# electricals_with_iPod_v2_5.net
KiCad netlist of a schematic drawn in EAGLE
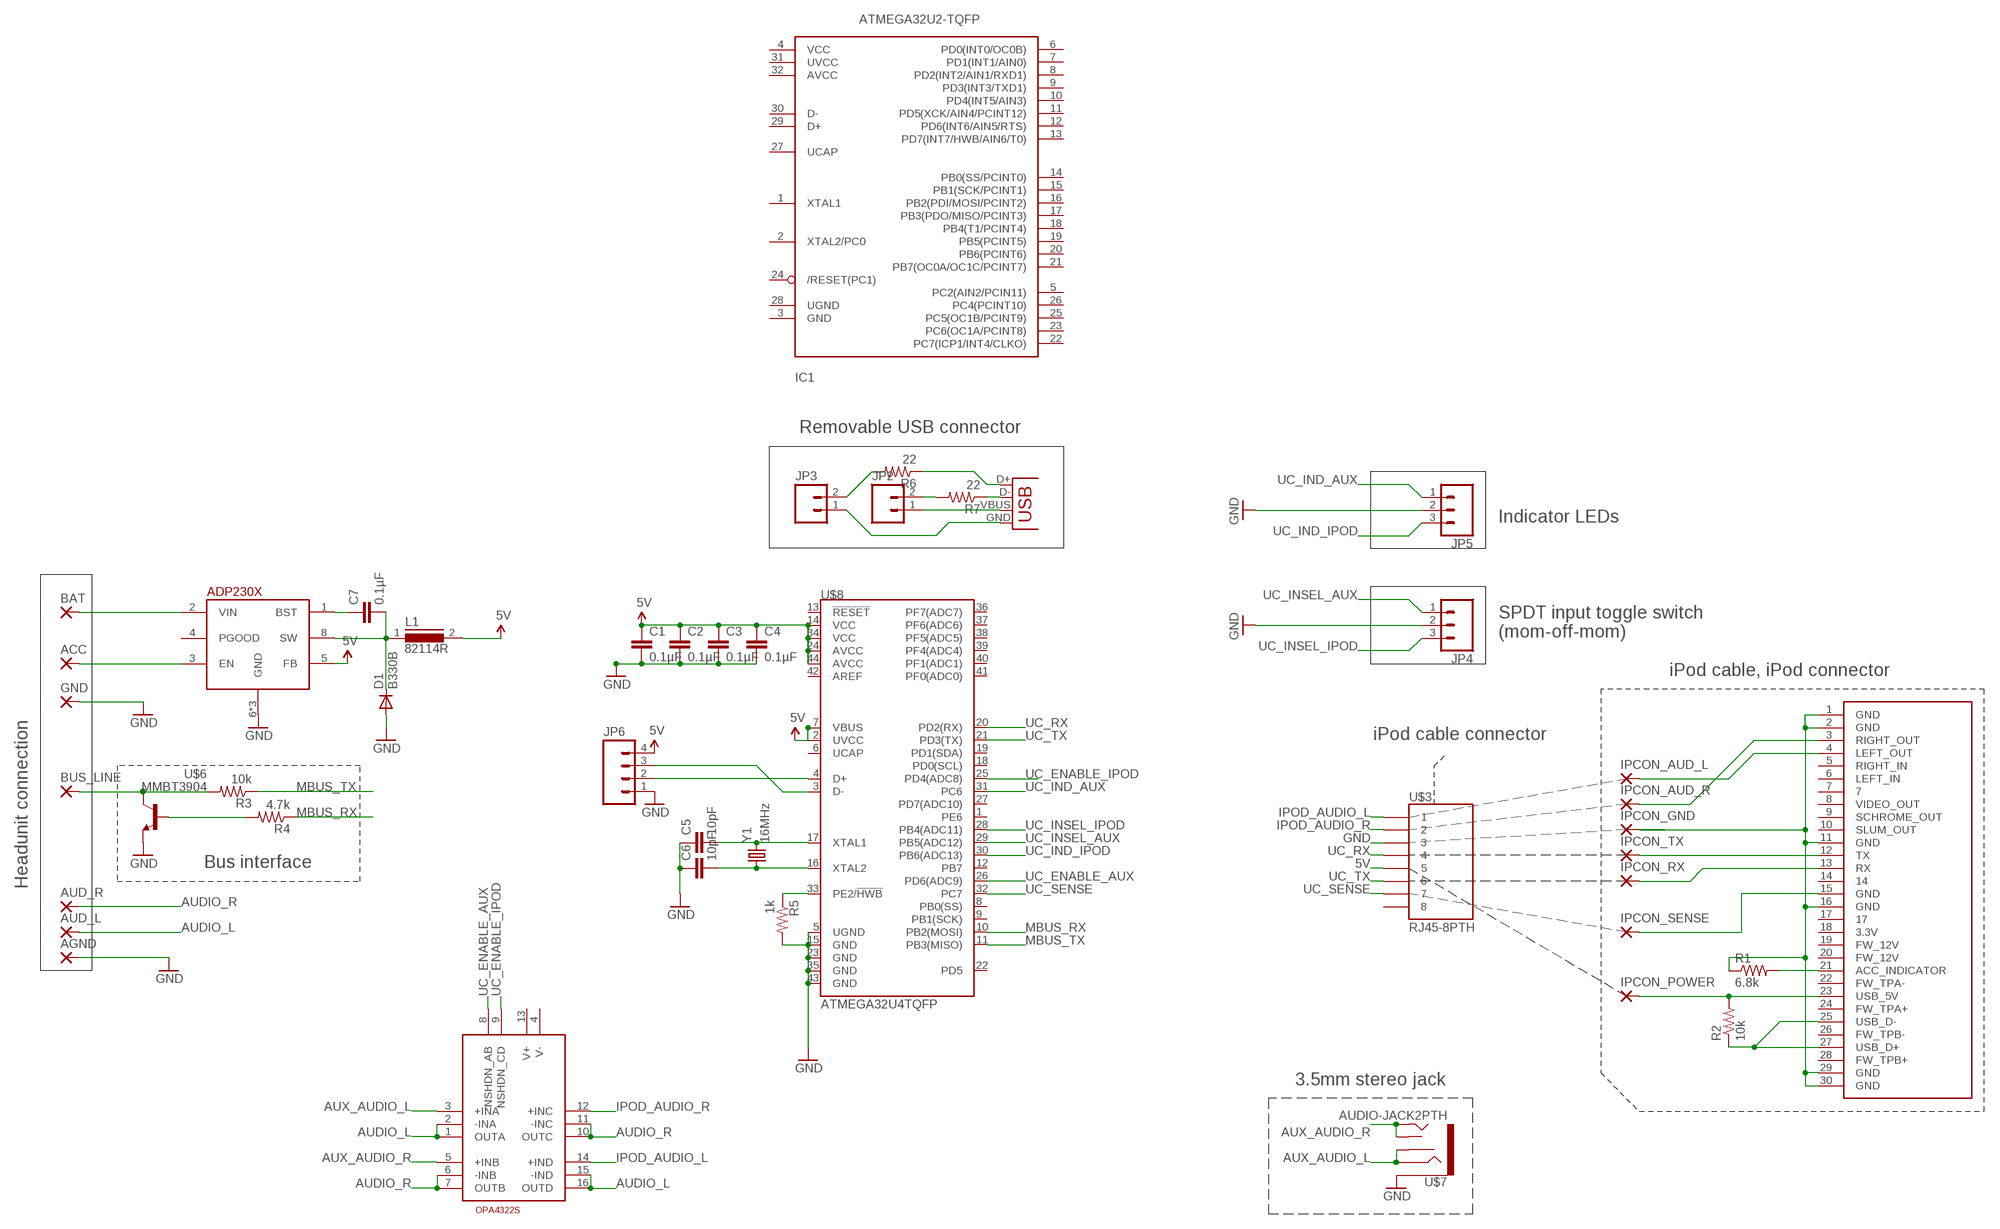
[diagram p0: schematic, sheet 1]

(export (version "E")
  (design (tool "Eeschema 10.0.6"))
  (components
    (comp (ref "ACC")
      (value "1,6/0,9")
      (footprint "eagle-import:1,6_0,9")
      (libsource (lib "eagle-import") (part "1,6/0,9"))
    )
    (comp (ref "AGND")
      (value "1,6/0,9")
      (footprint "eagle-import:1,6_0,9")
      (libsource (lib "eagle-import") (part "1,6/0,9"))
    )
    (comp (ref "AUD_L")
      (value "1,6/0,9")
      (footprint "eagle-import:1,6_0,9")
      (libsource (lib "eagle-import") (part "1,6/0,9"))
    )
    (comp (ref "AUD_R")
      (value "1,6/0,9")
      (footprint "eagle-import:1,6_0,9")
      (libsource (lib "eagle-import") (part "1,6/0,9"))
    )
    (comp (ref "BAT")
      (value "2,54/1,1")
      (footprint "eagle-import:2,54_1,1")
      (libsource (lib "eagle-import") (part "2,54/1,1"))
    )
    (comp (ref "BUS_LINE")
      (value "1,6/0,9")
      (footprint "eagle-import:1,6_0,9")
      (libsource (lib "eagle-import") (part "1,6/0,9"))
    )
    (comp (ref "C1")
      (value "0.1µF")
      (footprint "eagle-import:0805")
      (libsource (lib "eagle-import") (part "CAP0805"))
    )
    (comp (ref "C2")
      (value "0.1µF")
      (footprint "eagle-import:0805")
      (libsource (lib "eagle-import") (part "CAP0805"))
    )
    (comp (ref "C3")
      (value "0.1µF")
      (footprint "eagle-import:0805")
      (libsource (lib "eagle-import") (part "CAP0805"))
    )
    (comp (ref "C4")
      (value "0.1µF")
      (footprint "eagle-import:0805")
      (libsource (lib "eagle-import") (part "CAP0805"))
    )
    (comp (ref "C5")
      (value "10pF")
      (footprint "eagle-import:0805")
      (libsource (lib "eagle-import") (part "CAP0805"))
    )
    (comp (ref "C6")
      (value "10pF")
      (footprint "eagle-import:0805")
      (libsource (lib "eagle-import") (part "CAP0805"))
    )
    (comp (ref "C7")
      (value "0.1µF")
      (footprint "eagle-import:0805")
      (libsource (lib "eagle-import") (part "CAP0805"))
    )
    (comp (ref "D1")
      (value "B330B")
      (footprint "eagle-import:SMA-DIODE_ALT")
      (libsource (lib "eagle-import") (part "DIODESMA-ALT"))
    )
    (comp (ref "GND")
      (value "2,54/1,1")
      (footprint "eagle-import:2,54_1,1")
      (libsource (lib "eagle-import") (part "2,54/1,1"))
    )
    (comp (ref "IC1")
      (value "ATMEGA32U2-TQFP")
      (footprint "eagle-import:TQFP32-08")
      (libsource (lib "eagle-import") (part "ATMEGA32U2-TQFP"))
    )
    (comp (ref "IPCON_AUD_L")
      (value "1,6/0,9")
      (footprint "eagle-import:1,6_0,9")
      (libsource (lib "eagle-import") (part "1,6/0,9"))
    )
    (comp (ref "IPCON_AUD_R")
      (value "1,6/0,9")
      (footprint "eagle-import:1,6_0,9")
      (libsource (lib "eagle-import") (part "1,6/0,9"))
    )
    (comp (ref "IPCON_GND")
      (value "1,6/0,9")
      (footprint "eagle-import:1,6_0,9")
      (libsource (lib "eagle-import") (part "1,6/0,9"))
    )
    (comp (ref "IPCON_POWER")
      (value "1,6/0,9")
      (footprint "eagle-import:1,6_0,9")
      (libsource (lib "eagle-import") (part "1,6/0,9"))
    )
    (comp (ref "IPCON_RX")
      (value "1,6/0,9")
      (footprint "eagle-import:1,6_0,9")
      (libsource (lib "eagle-import") (part "1,6/0,9"))
    )
    (comp (ref "IPCON_SENSE")
      (value "1,6/0,9")
      (footprint "eagle-import:1,6_0,9")
      (libsource (lib "eagle-import") (part "1,6/0,9"))
    )
    (comp (ref "IPCON_TX")
      (value "1,6/0,9")
      (footprint "eagle-import:1,6_0,9")
      (libsource (lib "eagle-import") (part "1,6/0,9"))
    )
    (comp (ref "JP1")
      (value "USBSMD")
      (footprint "eagle-import:USB-MINIB")
      (libsource (lib "eagle-import") (part "USBSMD"))
    )
    (comp (ref "JP2")
      (value "M02POGO_PIN_HOLES_ONLY")
      (footprint "eagle-import:1X02_PP_HOLES_ONLY")
      (libsource (lib "eagle-import") (part "M02POGO_PIN_HOLES_ONLY"))
    )
    (comp (ref "JP3")
      (value "M02POGO_PIN_HOLES_ONLY")
      (footprint "eagle-import:1X02_PP_HOLES_ONLY")
      (libsource (lib "eagle-import") (part "M02POGO_PIN_HOLES_ONLY"))
    )
    (comp (ref "JP4")
      (value "M03LOCK")
      (footprint "eagle-import:1X03_LOCK")
      (libsource (lib "eagle-import") (part "M03LOCK"))
    )
    (comp (ref "JP5")
      (value "M03LOCK")
      (footprint "eagle-import:1X03_LOCK")
      (libsource (lib "eagle-import") (part "M03LOCK"))
    )
    (comp (ref "JP6")
      (value "M04PTH")
      (footprint "eagle-import:1X04")
      (libsource (lib "eagle-import") (part "M04PTH"))
    )
    (comp (ref "L1")
      (value "82114R")
      (footprint "eagle-import:82114R")
      (libsource (lib "eagle-import") (part "82114R"))
    )
    (comp (ref "R1")
      (value "6.8k")
      (footprint "eagle-import:0805")
      (libsource (lib "eagle-import") (part "RESISTOR0805-RES"))
    )
    (comp (ref "R2")
      (value "10k")
      (footprint "eagle-import:0805")
      (libsource (lib "eagle-import") (part "RESISTOR0805-RES"))
    )
    (comp (ref "R3")
      (value "10k")
      (footprint "eagle-import:0805")
      (libsource (lib "eagle-import") (part "RESISTOR0805-RES"))
    )
    (comp (ref "R4")
      (value "4.7k")
      (footprint "eagle-import:0805")
      (libsource (lib "eagle-import") (part "RESISTOR0805-RES"))
    )
    (comp (ref "R5")
      (value "1k")
      (footprint "eagle-import:0805")
      (libsource (lib "eagle-import") (part "RESISTOR0805-RES"))
    )
    (comp (ref "R6")
      (value "22")
      (footprint "eagle-import:0805")
      (libsource (lib "eagle-import") (part "RESISTOR0805-RES"))
    )
    (comp (ref "R7")
      (value "22")
      (footprint "eagle-import:0805")
      (libsource (lib "eagle-import") (part "RESISTOR0805-RES"))
    )
    (comp (ref "U$1")
      (value "IPOD_CONNECTOR_MALE")
      (footprint "eagle-import:IPOD_MALE_CONNECTOR")
      (libsource (lib "eagle-import") (part "IPOD_CONNECTOR_MALE"))
    )
    (comp (ref "U$3")
      (value "RJ45-8PTH")
      (footprint "eagle-import:RJ45-8")
      (libsource (lib "eagle-import") (part "RJ45-8PTH"))
    )
    (comp (ref "U$5")
      (value "ADP230X")
      (footprint "eagle-import:SO8-THERM")
      (libsource (lib "eagle-import") (part "ADP230X"))
    )
    (comp (ref "U$6")
      (value "MMBT3904")
      (footprint "eagle-import:SOT23-3")
      (libsource (lib "eagle-import") (part "MMBT3904"))
    )
    (comp (ref "U$7")
      (value "AUDIO-JACK2PTH")
      (footprint "eagle-import:AUDIO-JACK")
      (libsource (lib "eagle-import") (part "AUDIO-JACK2PTH"))
    )
    (comp (ref "U$8")
      (value "ATMEGA32U4TQFP")
      (footprint "eagle-import:SPARKFUN-DIGITALIC_TQFP44")
      (libsource (lib "eagle-import") (part "ATMEGA32U4TQFP"))
    )
    (comp (ref "U$11")
      (value "OPA4322S")
      (footprint "eagle-import:TSSOP16")
      (libsource (lib "eagle-import") (part "OPA4322S"))
    )
    (comp (ref "Y1")
      (value "16MHz")
      (footprint "eagle-import:CRYSTAL-SMD-5X3")
      (libsource (lib "eagle-import") (part "CRYSTAL5X3"))
    )
  )
  (nets
    (net (code "1") (name "/AUDIO_L") (class "Default")
      (node (ref "AUD_L") (pin "1") (pinfunction "P_1") (pintype "passive"))
      (node (ref "U$11") (pin "1") (pinfunction "OUTA_1") (pintype "bidirectional"))
      (node (ref "U$11") (pin "15") (pinfunction "-IND_15") (pintype "bidirectional"))
      (node (ref "U$11") (pin "16") (pinfunction "OUTD_16") (pintype "bidirectional"))
      (node (ref "U$11") (pin "2") (pinfunction "-INA_2") (pintype "bidirectional"))
    )
    (net (code "2") (name "/AUDIO_R") (class "Default")
      (node (ref "AUD_R") (pin "1") (pinfunction "P_1") (pintype "passive"))
      (node (ref "U$11") (pin "10") (pinfunction "OUTC_10") (pintype "bidirectional"))
      (node (ref "U$11") (pin "11") (pinfunction "-INC_11") (pintype "bidirectional"))
      (node (ref "U$11") (pin "6") (pinfunction "-INB_6") (pintype "bidirectional"))
      (node (ref "U$11") (pin "7") (pinfunction "OUTB_7") (pintype "bidirectional"))
    )
    (net (code "3") (name "/AUX_AUDIO_L") (class "Default")
      (node (ref "U$11") (pin "3") (pinfunction "+INA_3") (pintype "bidirectional"))
      (node (ref "U$7") (pin "RING") (pinfunction "RING_RING") (pintype "bidirectional"))
      (node (ref "U$7") (pin "RSH") (pinfunction "RSH_RSH") (pintype "bidirectional"))
    )
    (net (code "4") (name "/AUX_AUDIO_R") (class "Default")
      (node (ref "U$11") (pin "5") (pinfunction "+INB_5") (pintype "bidirectional"))
      (node (ref "U$7") (pin "TIP") (pinfunction "TIP_TIP") (pintype "bidirectional"))
      (node (ref "U$7") (pin "TSH") (pinfunction "TSH_TSH") (pintype "bidirectional"))
    )
    (net (code "5") (name "/IPOD_AUDIO_L") (class "Default")
      (node (ref "U$11") (pin "14") (pinfunction "+IND_14") (pintype "bidirectional"))
      (node (ref "U$3") (pin "1") (pinfunction "1_1") (pintype "bidirectional"))
    )
    (net (code "6") (name "/IPOD_AUDIO_R") (class "Default")
      (node (ref "U$11") (pin "12") (pinfunction "+INC_12") (pintype "bidirectional"))
      (node (ref "U$3") (pin "2") (pinfunction "2_2") (pintype "bidirectional"))
    )
    (net (code "7") (name "/MBUS_RX") (class "Default")
      (node (ref "R4") (pin "1") (pinfunction "1_1") (pintype "passive"))
      (node (ref "U$8") (pin "10") (pinfunction "PB2(MOSI)_10") (pintype "bidirectional"))
    )
    (net (code "8") (name "/MBUS_TX") (class "Default")
      (node (ref "R3") (pin "1") (pinfunction "1_1") (pintype "passive"))
      (node (ref "U$8") (pin "11") (pinfunction "PB3(MISO)_11") (pintype "bidirectional"))
    )
    (net (code "9") (name "/UC_ENABLE_AUX") (class "Default")
      (node (ref "U$11") (pin "8") (pinfunction "NSHDN_AB_8") (pintype "bidirectional"))
      (node (ref "U$8") (pin "26") (pinfunction "PD6(ADC9)_26") (pintype "bidirectional"))
    )
    (net (code "10") (name "/UC_ENABLE_IPOD") (class "Default")
      (node (ref "U$11") (pin "9") (pinfunction "NSHDN_CD_9") (pintype "bidirectional"))
      (node (ref "U$8") (pin "25") (pinfunction "PD4(ADC8)_25") (pintype "bidirectional"))
    )
    (net (code "11") (name "/UC_IND_AUX") (class "Default")
      (node (ref "JP5") (pin "1") (pinfunction "1_1") (pintype "passive"))
      (node (ref "U$8") (pin "31") (pinfunction "PC6_31") (pintype "bidirectional"))
    )
    (net (code "12") (name "/UC_IND_IPOD") (class "Default")
      (node (ref "JP5") (pin "3") (pinfunction "3_3") (pintype "passive"))
      (node (ref "U$8") (pin "30") (pinfunction "PB6(ADC13)_30") (pintype "bidirectional"))
    )
    (net (code "13") (name "/UC_INSEL_AUX") (class "Default")
      (node (ref "JP4") (pin "1") (pinfunction "1_1") (pintype "passive"))
      (node (ref "U$8") (pin "29") (pinfunction "PB5(ADC12)_29") (pintype "bidirectional"))
    )
    (net (code "14") (name "/UC_INSEL_IPOD") (class "Default")
      (node (ref "JP4") (pin "3") (pinfunction "3_3") (pintype "passive"))
      (node (ref "U$8") (pin "28") (pinfunction "PB4(ADC11)_28") (pintype "bidirectional"))
    )
    (net (code "15") (name "/UC_RX") (class "Default")
      (node (ref "U$3") (pin "4") (pinfunction "4_4") (pintype "bidirectional"))
      (node (ref "U$8") (pin "20") (pinfunction "PD2(RX)_20") (pintype "bidirectional"))
    )
    (net (code "16") (name "/UC_SENSE") (class "Default")
      (node (ref "U$3") (pin "7") (pinfunction "7_7") (pintype "bidirectional"))
      (node (ref "U$8") (pin "32") (pinfunction "PC7_32") (pintype "bidirectional"))
    )
    (net (code "17") (name "/UC_TX") (class "Default")
      (node (ref "U$3") (pin "6") (pinfunction "6_6") (pintype "bidirectional"))
      (node (ref "U$8") (pin "21") (pinfunction "PD3(TX)_21") (pintype "bidirectional"))
    )
    (net (code "18") (name "5V") (class "Default")
      (node (ref "C1") (pin "1") (pinfunction "1_1") (pintype "passive"))
      (node (ref "C2") (pin "1") (pinfunction "1_1") (pintype "passive"))
      (node (ref "C3") (pin "1") (pinfunction "1_1") (pintype "passive"))
      (node (ref "C4") (pin "1") (pinfunction "1_1") (pintype "passive"))
      (node (ref "JP6") (pin "4") (pinfunction "4_4") (pintype "passive"))
      (node (ref "L1") (pin "2") (pinfunction "2_2") (pintype "passive"))
      (node (ref "U$3") (pin "5") (pinfunction "5_5") (pintype "bidirectional"))
      (node (ref "U$5") (pin "5") (pinfunction "FB_5") (pintype "bidirectional"))
      (node (ref "U$8") (pin "14") (pinfunction "VCC_14") (pintype "bidirectional"))
      (node (ref "U$8") (pin "2") (pinfunction "UVCC_2") (pintype "bidirectional"))
      (node (ref "U$8") (pin "24") (pinfunction "AVCC_24") (pintype "bidirectional"))
      (node (ref "U$8") (pin "34") (pinfunction "VCC_34") (pintype "bidirectional"))
      (node (ref "U$8") (pin "44") (pinfunction "AVCC_44") (pintype "bidirectional"))
      (node (ref "U$8") (pin "7") (pinfunction "VBUS_7") (pintype "bidirectional"))
    )
    (net (code "19") (name "GND") (class "Default")
      (node (ref "AGND") (pin "1") (pinfunction "P_1") (pintype "passive"))
      (node (ref "C1") (pin "2") (pinfunction "2_2") (pintype "passive"))
      (node (ref "C2") (pin "2") (pinfunction "2_2") (pintype "passive"))
      (node (ref "C3") (pin "2") (pinfunction "2_2") (pintype "passive"))
      (node (ref "C4") (pin "2") (pinfunction "2_2") (pintype "passive"))
      (node (ref "C5") (pin "1") (pinfunction "1_1") (pintype "passive"))
      (node (ref "C6") (pin "1") (pinfunction "1_1") (pintype "passive"))
      (node (ref "D1") (pin "A") (pinfunction "A_A") (pintype "passive"))
      (node (ref "GND") (pin "1") (pinfunction "P_1") (pintype "passive"))
      (node (ref "JP4") (pin "2") (pinfunction "2_2") (pintype "passive"))
      (node (ref "JP5") (pin "2") (pinfunction "2_2") (pintype "passive"))
      (node (ref "JP6") (pin "1") (pinfunction "1_1") (pintype "passive"))
      (node (ref "R5") (pin "2") (pinfunction "2_2") (pintype "passive"))
      (node (ref "U$3") (pin "3") (pinfunction "3_3") (pintype "bidirectional"))
      (node (ref "U$5") (pin "6") (pinfunction "GND_6") (pintype "bidirectional"))
      (node (ref "U$5") (pin "7") (pinfunction "GND_7") (pintype "bidirectional"))
      (node (ref "U$5") (pin "PAD") (pinfunction "GND_PAD") (pintype "bidirectional"))
      (node (ref "U$6") (pin "2") (pinfunction "E_2") (pintype "passive"))
      (node (ref "U$7") (pin "SLEEVE") (pinfunction "SLEEVE_SLEEVE") (pintype "bidirectional"))
      (node (ref "U$8") (pin "15") (pinfunction "GND_15") (pintype "bidirectional"))
      (node (ref "U$8") (pin "23") (pinfunction "GND_23") (pintype "bidirectional"))
      (node (ref "U$8") (pin "35") (pinfunction "GND_35") (pintype "bidirectional"))
      (node (ref "U$8") (pin "43") (pinfunction "GND_43") (pintype "bidirectional"))
      (node (ref "U$8") (pin "5") (pinfunction "UGND_5") (pintype "bidirectional"))
    )
    (net (code "20") (name "Net-(ACC-P)") (class "Default")
      (node (ref "ACC") (pin "1") (pinfunction "P_1") (pintype "passive"))
      (node (ref "U$5") (pin "3") (pinfunction "EN_3") (pintype "bidirectional"))
    )
    (net (code "21") (name "Net-(BAT-P)") (class "Default")
      (node (ref "BAT") (pin "1") (pinfunction "P_1") (pintype "passive"))
      (node (ref "U$5") (pin "2") (pinfunction "VIN_2") (pintype "bidirectional"))
    )
    (net (code "22") (name "Net-(BUS_LINE-P)") (class "Default")
      (node (ref "BUS_LINE") (pin "1") (pinfunction "P_1") (pintype "passive"))
      (node (ref "R3") (pin "2") (pinfunction "2_2") (pintype "passive"))
      (node (ref "U$6") (pin "3") (pinfunction "C_3") (pintype "passive"))
    )
    (net (code "23") (name "Net-(IPCON_AUD_L-P)") (class "Default")
      (node (ref "IPCON_AUD_L") (pin "1") (pinfunction "P_1") (pintype "passive"))
      (node (ref "U$1") (pin "4") (pinfunction "LEFT_OUT_4") (pintype "bidirectional"))
    )
    (net (code "24") (name "Net-(IPCON_AUD_R-P)") (class "Default")
      (node (ref "IPCON_AUD_R") (pin "1") (pinfunction "P_1") (pintype "passive"))
      (node (ref "U$1") (pin "3") (pinfunction "RIGHT_OUT_3") (pintype "bidirectional"))
    )
    (net (code "25") (name "Net-(IPCON_GND-P)") (class "Default")
      (node (ref "IPCON_GND") (pin "1") (pinfunction "P_1") (pintype "passive"))
      (node (ref "R1") (pin "1") (pinfunction "1_1") (pintype "passive"))
      (node (ref "U$1") (pin "1") (pinfunction "GND_1") (pintype "bidirectional"))
      (node (ref "U$1") (pin "11") (pinfunction "GND_11") (pintype "bidirectional"))
      (node (ref "U$1") (pin "16") (pinfunction "GND_16") (pintype "bidirectional"))
      (node (ref "U$1") (pin "2") (pinfunction "GND_2") (pintype "bidirectional"))
      (node (ref "U$1") (pin "29") (pinfunction "GND_29") (pintype "bidirectional"))
      (node (ref "U$1") (pin "30") (pinfunction "GND_30") (pintype "bidirectional"))
    )
    (net (code "26") (name "Net-(IPCON_POWER-P)") (class "Default")
      (node (ref "IPCON_POWER") (pin "1") (pinfunction "P_1") (pintype "passive"))
      (node (ref "R2") (pin "2") (pinfunction "2_2") (pintype "passive"))
      (node (ref "U$1") (pin "23") (pinfunction "USB_5V_23") (pintype "bidirectional"))
    )
    (net (code "27") (name "Net-(IPCON_RX-P)") (class "Default")
      (node (ref "IPCON_RX") (pin "1") (pinfunction "P_1") (pintype "passive"))
      (node (ref "U$1") (pin "13") (pinfunction "RX_13") (pintype "bidirectional"))
    )
    (net (code "28") (name "Net-(IPCON_SENSE-P)") (class "Default")
      (node (ref "IPCON_SENSE") (pin "1") (pinfunction "P_1") (pintype "passive"))
      (node (ref "U$1") (pin "15") (pinfunction "GND_15") (pintype "bidirectional"))
    )
    (net (code "29") (name "Net-(IPCON_TX-P)") (class "Default")
      (node (ref "IPCON_TX") (pin "1") (pinfunction "P_1") (pintype "passive"))
      (node (ref "U$1") (pin "12") (pinfunction "TX_12") (pintype "bidirectional"))
    )
    (net (code "30") (name "Net-(JP1-PadD+)") (class "Default")
      (node (ref "JP1") (pin "D+") (pinfunction "D+_D+") (pintype "bidirectional"))
      (node (ref "R6") (pin "1") (pinfunction "1_1") (pintype "passive"))
    )
    (net (code "31") (name "Net-(JP1-PadD-)") (class "Default")
      (node (ref "JP1") (pin "D-") (pinfunction "D-_D-") (pintype "bidirectional"))
      (node (ref "R7") (pin "1") (pinfunction "1_1") (pintype "passive"))
    )
    (net (code "32") (name "Net-(JP1-PadGND)") (class "Default")
      (node (ref "JP1") (pin "GND") (pinfunction "GND_GND") (pintype "bidirectional"))
      (node (ref "JP3") (pin "1") (pinfunction "1_1") (pintype "passive"))
    )
    (net (code "33") (name "Net-(JP1-PadVBUS)") (class "Default")
      (node (ref "JP1") (pin "VBUS") (pinfunction "VBUS_VBUS") (pintype "bidirectional"))
      (node (ref "JP2") (pin "1") (pinfunction "1_1") (pintype "passive"))
    )
    (net (code "34") (name "Net-(JP2-Pad2)") (class "Default")
      (node (ref "JP2") (pin "2") (pinfunction "2_2") (pintype "passive"))
      (node (ref "R7") (pin "2") (pinfunction "2_2") (pintype "passive"))
    )
    (net (code "35") (name "Net-(JP3-Pad2)") (class "Default")
      (node (ref "JP3") (pin "2") (pinfunction "2_2") (pintype "passive"))
      (node (ref "R6") (pin "2") (pinfunction "2_2") (pintype "passive"))
    )
    (net (code "36") (name "Net-(U$1-ACC_INDICATOR)") (class "Default")
      (node (ref "R1") (pin "2") (pinfunction "2_2") (pintype "passive"))
      (node (ref "U$1") (pin "21") (pinfunction "ACC_INDICATOR_21") (pintype "bidirectional"))
    )
    (net (code "37") (name "Net-(U$1-USB_D+)") (class "Default")
      (node (ref "R2") (pin "1") (pinfunction "1_1") (pintype "passive"))
      (node (ref "U$1") (pin "25") (pinfunction "USB_D-_25") (pintype "bidirectional"))
      (node (ref "U$1") (pin "27") (pinfunction "USB_D+_27") (pintype "bidirectional"))
    )
    (net (code "38") (name "Net-(U$5-BST)") (class "Default")
      (node (ref "C7") (pin "1") (pinfunction "1_1") (pintype "passive"))
      (node (ref "U$5") (pin "1") (pinfunction "BST_1") (pintype "bidirectional"))
    )
    (net (code "39") (name "Net-(U$5-SW)") (class "Default")
      (node (ref "C7") (pin "2") (pinfunction "2_2") (pintype "passive"))
      (node (ref "D1") (pin "C") (pinfunction "C_C") (pintype "passive"))
      (node (ref "L1") (pin "1") (pinfunction "1_1") (pintype "passive"))
      (node (ref "U$5") (pin "8") (pinfunction "SW_8") (pintype "bidirectional"))
    )
    (net (code "40") (name "Net-(U$6-B)") (class "Default")
      (node (ref "R4") (pin "2") (pinfunction "2_2") (pintype "passive"))
      (node (ref "U$6") (pin "1") (pinfunction "B_1") (pintype "passive"))
    )
    (net (code "41") (name "Net-(U$8-D+)") (class "Default")
      (node (ref "JP6") (pin "2") (pinfunction "2_2") (pintype "passive"))
      (node (ref "U$8") (pin "4") (pinfunction "D+_4") (pintype "bidirectional"))
    )
    (net (code "42") (name "Net-(U$8-D-)") (class "Default")
      (node (ref "JP6") (pin "3") (pinfunction "3_3") (pintype "passive"))
      (node (ref "U$8") (pin "3") (pinfunction "D-_3") (pintype "bidirectional"))
    )
    (net (code "43") (name "Net-(U$8-PE2{slash}~{HWB})") (class "Default")
      (node (ref "R5") (pin "1") (pinfunction "1_1") (pintype "passive"))
      (node (ref "U$8") (pin "33") (pinfunction "PE2/~{HWB}_33") (pintype "bidirectional"))
    )
    (net (code "44") (name "Net-(U$8-XTAL1)") (class "Default")
      (node (ref "C5") (pin "2") (pinfunction "2_2") (pintype "passive"))
      (node (ref "U$8") (pin "17") (pinfunction "XTAL1_17") (pintype "bidirectional"))
      (node (ref "Y1") (pin "3") (pinfunction "2_3") (pintype "passive"))
    )
    (net (code "45") (name "Net-(U$8-XTAL2)") (class "Default")
      (node (ref "C6") (pin "2") (pinfunction "2_2") (pintype "passive"))
      (node (ref "U$8") (pin "16") (pinfunction "XTAL2_16") (pintype "bidirectional"))
      (node (ref "Y1") (pin "1") (pinfunction "1_1") (pintype "passive"))
    )
    (net (code "46") (name "unconnected-(IC1-AVCC-Pad32)") (class "Default")
      (node (ref "IC1") (pin "32") (pinfunction "AVCC_32") (pintype "bidirectional"))
    )
    (net (code "47") (name "unconnected-(IC1-D+-Pad29)") (class "Default")
      (node (ref "IC1") (pin "29") (pinfunction "D+_29") (pintype "bidirectional"))
    )
    (net (code "48") (name "unconnected-(IC1-D--Pad30)") (class "Default")
      (node (ref "IC1") (pin "30") (pinfunction "D-_30") (pintype "bidirectional"))
    )
    (net (code "49") (name "unconnected-(IC1-GND-Pad3)") (class "Default")
      (node (ref "IC1") (pin "3") (pinfunction "GND_3") (pintype "bidirectional"))
    )
    (net (code "50") (name "unconnected-(IC1-PB0(SS{slash}PCINT0)-Pad14)") (class "Default")
      (node (ref "IC1") (pin "14") (pinfunction "PB0(SS/PCINT0)_14") (pintype "bidirectional"))
    )
    (net (code "51") (name "unconnected-(IC1-PB1(SCK{slash}PCINT1)-Pad15)") (class "Default")
      (node (ref "IC1") (pin "15") (pinfunction "PB1(SCK/PCINT1)_15") (pintype "bidirectional"))
    )
    (net (code "52") (name "unconnected-(IC1-PB2(PDI{slash}MOSI{slash}PCINT2)-Pad16)") (class "Default")
      (node (ref "IC1") (pin "16") (pinfunction "PB2(PDI/MOSI/PCINT2)_16") (pintype "bidirectional"))
    )
    (net (code "53") (name "unconnected-(IC1-PB3(PDO{slash}MISO{slash}PCINT3)-Pad17)") (class "Default")
      (node (ref "IC1") (pin "17") (pinfunction "PB3(PDO/MISO/PCINT3)_17") (pintype "bidirectional"))
    )
    (net (code "54") (name "unconnected-(IC1-PB4(T1{slash}PCINT4)-Pad18)") (class "Default")
      (node (ref "IC1") (pin "18") (pinfunction "PB4(T1/PCINT4)_18") (pintype "bidirectional"))
    )
    (net (code "55") (name "unconnected-(IC1-PB5(PCINT5)-Pad19)") (class "Default")
      (node (ref "IC1") (pin "19") (pinfunction "PB5(PCINT5)_19") (pintype "bidirectional"))
    )
    (net (code "56") (name "unconnected-(IC1-PB6(PCINT6)-Pad20)") (class "Default")
      (node (ref "IC1") (pin "20") (pinfunction "PB6(PCINT6)_20") (pintype "bidirectional"))
    )
    (net (code "57") (name "unconnected-(IC1-PB7(OC0A{slash}OC1C{slash}PCINT7)-Pad21)") (class "Default")
      (node (ref "IC1") (pin "21") (pinfunction "PB7(OC0A/OC1C/PCINT7)_21") (pintype "bidirectional"))
    )
    (net (code "58") (name "unconnected-(IC1-PC2(AIN2{slash}PCIN11)-Pad5)") (class "Default")
      (node (ref "IC1") (pin "5") (pinfunction "PC2(AIN2/PCIN11)_5") (pintype "bidirectional"))
    )
    (net (code "59") (name "unconnected-(IC1-PC4(PCINT10)-Pad26)") (class "Default")
      (node (ref "IC1") (pin "26") (pinfunction "PC4(PCINT10)_26") (pintype "bidirectional"))
    )
    (net (code "60") (name "unconnected-(IC1-PC5(OC1B{slash}PCINT9)-Pad25)") (class "Default")
      (node (ref "IC1") (pin "25") (pinfunction "PC5(OC1B/PCINT9)_25") (pintype "bidirectional"))
    )
    (net (code "61") (name "unconnected-(IC1-PC6(OC1A{slash}PCINT8)-Pad23)") (class "Default")
      (node (ref "IC1") (pin "23") (pinfunction "PC6(OC1A/PCINT8)_23") (pintype "bidirectional"))
    )
    (net (code "62") (name "unconnected-(IC1-PC7(ICP1{slash}INT4{slash}CLKO)-Pad22)") (class "Default")
      (node (ref "IC1") (pin "22") (pinfunction "PC7(ICP1/INT4/CLKO)_22") (pintype "bidirectional"))
    )
    (net (code "63") (name "unconnected-(IC1-PD0(INT0{slash}OC0B)-Pad6)") (class "Default")
      (node (ref "IC1") (pin "6") (pinfunction "PD0(INT0/OC0B)_6") (pintype "bidirectional"))
    )
    (net (code "64") (name "unconnected-(IC1-PD1(INT1{slash}AIN0)-Pad7)") (class "Default")
      (node (ref "IC1") (pin "7") (pinfunction "PD1(INT1/AIN0)_7") (pintype "bidirectional"))
    )
    (net (code "65") (name "unconnected-(IC1-PD2(INT2{slash}AIN1{slash}RXD1)-Pad8)") (class "Default")
      (node (ref "IC1") (pin "8") (pinfunction "PD2(INT2/AIN1/RXD1)_8") (pintype "bidirectional"))
    )
    (net (code "66") (name "unconnected-(IC1-PD3(INT3{slash}TXD1)-Pad9)") (class "Default")
      (node (ref "IC1") (pin "9") (pinfunction "PD3(INT3/TXD1)_9") (pintype "bidirectional"))
    )
    (net (code "67") (name "unconnected-(IC1-PD4(INT5{slash}AIN3)-Pad10)") (class "Default")
      (node (ref "IC1") (pin "10") (pinfunction "PD4(INT5/AIN3)_10") (pintype "bidirectional"))
    )
    (net (code "68") (name "unconnected-(IC1-PD5(XCK{slash}AIN4{slash}PCINT12)-Pad11)") (class "Default")
      (node (ref "IC1") (pin "11") (pinfunction "PD5(XCK/AIN4/PCINT12)_11") (pintype "bidirectional"))
    )
    (net (code "69") (name "unconnected-(IC1-PD6(INT6{slash}AIN5{slash}RTS)-Pad12)") (class "Default")
      (node (ref "IC1") (pin "12") (pinfunction "PD6(INT6/AIN5/RTS)_12") (pintype "bidirectional"))
    )
    (net (code "70") (name "unconnected-(IC1-PD7(INT7{slash}HWB{slash}AIN6{slash}T0)-Pad13)") (class "Default")
      (node (ref "IC1") (pin "13") (pinfunction "PD7(INT7/HWB/AIN6/T0)_13") (pintype "bidirectional"))
    )
    (net (code "71") (name "unconnected-(IC1-UCAP-Pad27)") (class "Default")
      (node (ref "IC1") (pin "27") (pinfunction "UCAP_27") (pintype "bidirectional"))
    )
    (net (code "72") (name "unconnected-(IC1-UGND-Pad28)") (class "Default")
      (node (ref "IC1") (pin "28") (pinfunction "UGND_28") (pintype "bidirectional"))
    )
    (net (code "73") (name "unconnected-(IC1-UVCC-Pad31)") (class "Default")
      (node (ref "IC1") (pin "31") (pinfunction "UVCC_31") (pintype "bidirectional"))
    )
    (net (code "74") (name "unconnected-(IC1-VCC-Pad4)") (class "Default")
      (node (ref "IC1") (pin "4") (pinfunction "VCC_4") (pintype "bidirectional"))
    )
    (net (code "75") (name "unconnected-(IC1-XTAL1-Pad1)") (class "Default")
      (node (ref "IC1") (pin "1") (pinfunction "XTAL1_1") (pintype "bidirectional"))
    )
    (net (code "76") (name "unconnected-(IC1-XTAL2{slash}PC0-Pad2)") (class "Default")
      (node (ref "IC1") (pin "2") (pinfunction "XTAL2/PC0_2") (pintype "bidirectional"))
    )
    (net (code "77") (name "unconnected-(IC1-{slash}RESET(PC1)-Pad24)") (class "Default")
      (node (ref "IC1") (pin "24") (pinfunction "/RESET(PC1)_24") (pintype "bidirectional"))
    )
    (net (code "78") (name "unconnected-(U$1-3.3V-Pad18)") (class "Default")
      (node (ref "U$1") (pin "18") (pinfunction "3.3V_18") (pintype "bidirectional"))
    )
    (net (code "79") (name "unconnected-(U$1-FW_12V-Pad19)") (class "Default")
      (node (ref "U$1") (pin "19") (pinfunction "FW_12V_19") (pintype "bidirectional"))
    )
    (net (code "80") (name "unconnected-(U$1-FW_12V-Pad20)") (class "Default")
      (node (ref "U$1") (pin "20") (pinfunction "FW_12V_20") (pintype "bidirectional"))
    )
    (net (code "81") (name "unconnected-(U$1-FW_TPA+-Pad24)") (class "Default")
      (node (ref "U$1") (pin "24") (pinfunction "FW_TPA+_24") (pintype "bidirectional"))
    )
    (net (code "82") (name "unconnected-(U$1-FW_TPA--Pad22)") (class "Default")
      (node (ref "U$1") (pin "22") (pinfunction "FW_TPA-_22") (pintype "bidirectional"))
    )
    (net (code "83") (name "unconnected-(U$1-FW_TPB+-Pad28)") (class "Default")
      (node (ref "U$1") (pin "28") (pinfunction "FW_TPB+_28") (pintype "bidirectional"))
    )
    (net (code "84") (name "unconnected-(U$1-FW_TPB--Pad26)") (class "Default")
      (node (ref "U$1") (pin "26") (pinfunction "FW_TPB-_26") (pintype "bidirectional"))
    )
    (net (code "85") (name "unconnected-(U$1-LEFT_IN-Pad6)") (class "Default")
      (node (ref "U$1") (pin "6") (pinfunction "LEFT_IN_6") (pintype "bidirectional"))
    )
    (net (code "86") (name "unconnected-(U$1-Pad7)") (class "Default")
      (node (ref "U$1") (pin "7") (pinfunction "7_7") (pintype "bidirectional"))
    )
    (net (code "87") (name "unconnected-(U$1-Pad14)") (class "Default")
      (node (ref "U$1") (pin "14") (pinfunction "14_14") (pintype "bidirectional"))
    )
    (net (code "88") (name "unconnected-(U$1-Pad17)") (class "Default")
      (node (ref "U$1") (pin "17") (pinfunction "17_17") (pintype "bidirectional"))
    )
    (net (code "89") (name "unconnected-(U$1-RIGHT_IN-Pad5)") (class "Default")
      (node (ref "U$1") (pin "5") (pinfunction "RIGHT_IN_5") (pintype "bidirectional"))
    )
    (net (code "90") (name "unconnected-(U$1-SCHROME_OUT-Pad9)") (class "Default")
      (node (ref "U$1") (pin "9") (pinfunction "SCHROME_OUT_9") (pintype "bidirectional"))
    )
    (net (code "91") (name "unconnected-(U$1-SLUM_OUT-Pad10)") (class "Default")
      (node (ref "U$1") (pin "10") (pinfunction "SLUM_OUT_10") (pintype "bidirectional"))
    )
    (net (code "92") (name "unconnected-(U$1-VIDEO_OUT-Pad8)") (class "Default")
      (node (ref "U$1") (pin "8") (pinfunction "VIDEO_OUT_8") (pintype "bidirectional"))
    )
    (net (code "93") (name "unconnected-(U$3-Pad8)") (class "Default")
      (node (ref "U$3") (pin "8") (pinfunction "8_8") (pintype "bidirectional"))
    )
    (net (code "94") (name "unconnected-(U$5-PGOOD-Pad4)") (class "Default")
      (node (ref "U$5") (pin "4") (pinfunction "PGOOD_4") (pintype "bidirectional"))
    )
    (net (code "95") (name "unconnected-(U$8-AREF-Pad42)") (class "Default")
      (node (ref "U$8") (pin "42") (pinfunction "AREF_42") (pintype "bidirectional"))
    )
    (net (code "96") (name "unconnected-(U$8-PB0(SS)-Pad8)") (class "Default")
      (node (ref "U$8") (pin "8") (pinfunction "PB0(SS)_8") (pintype "bidirectional"))
    )
    (net (code "97") (name "unconnected-(U$8-PB1(SCK)-Pad9)") (class "Default")
      (node (ref "U$8") (pin "9") (pinfunction "PB1(SCK)_9") (pintype "bidirectional"))
    )
    (net (code "98") (name "unconnected-(U$8-PB7-Pad12)") (class "Default")
      (node (ref "U$8") (pin "12") (pinfunction "PB7_12") (pintype "bidirectional"))
    )
    (net (code "99") (name "unconnected-(U$8-PD0(SCL)-Pad18)") (class "Default")
      (node (ref "U$8") (pin "18") (pinfunction "PD0(SCL)_18") (pintype "bidirectional"))
    )
    (net (code "100") (name "unconnected-(U$8-PD1(SDA)-Pad19)") (class "Default")
      (node (ref "U$8") (pin "19") (pinfunction "PD1(SDA)_19") (pintype "bidirectional"))
    )
    (net (code "101") (name "unconnected-(U$8-PD5-Pad22)") (class "Default")
      (node (ref "U$8") (pin "22") (pinfunction "PD5_22") (pintype "bidirectional"))
    )
    (net (code "102") (name "unconnected-(U$8-PD7(ADC10)-Pad27)") (class "Default")
      (node (ref "U$8") (pin "27") (pinfunction "PD7(ADC10)_27") (pintype "bidirectional"))
    )
    (net (code "103") (name "unconnected-(U$8-PE6-Pad1)") (class "Default")
      (node (ref "U$8") (pin "1") (pinfunction "PE6_1") (pintype "bidirectional"))
    )
    (net (code "104") (name "unconnected-(U$8-PF0(ADC0)-Pad41)") (class "Default")
      (node (ref "U$8") (pin "41") (pinfunction "PF0(ADC0)_41") (pintype "bidirectional"))
    )
    (net (code "105") (name "unconnected-(U$8-PF1(ADC1)-Pad40)") (class "Default")
      (node (ref "U$8") (pin "40") (pinfunction "PF1(ADC1)_40") (pintype "bidirectional"))
    )
    (net (code "106") (name "unconnected-(U$8-PF4(ADC4)-Pad39)") (class "Default")
      (node (ref "U$8") (pin "39") (pinfunction "PF4(ADC4)_39") (pintype "bidirectional"))
    )
    (net (code "107") (name "unconnected-(U$8-PF5(ADC5)-Pad38)") (class "Default")
      (node (ref "U$8") (pin "38") (pinfunction "PF5(ADC5)_38") (pintype "bidirectional"))
    )
    (net (code "108") (name "unconnected-(U$8-PF6(ADC6)-Pad37)") (class "Default")
      (node (ref "U$8") (pin "37") (pinfunction "PF6(ADC6)_37") (pintype "bidirectional"))
    )
    (net (code "109") (name "unconnected-(U$8-PF7(ADC7)-Pad36)") (class "Default")
      (node (ref "U$8") (pin "36") (pinfunction "PF7(ADC7)_36") (pintype "bidirectional"))
    )
    (net (code "110") (name "unconnected-(U$8-UCAP-Pad6)") (class "Default")
      (node (ref "U$8") (pin "6") (pinfunction "UCAP_6") (pintype "bidirectional"))
    )
    (net (code "111") (name "unconnected-(U$8-~{RESET}-Pad13)") (class "Default")
      (node (ref "U$8") (pin "13") (pinfunction "~{RESET}_13") (pintype "bidirectional"))
    )
    (net (code "112") (name "unconnected-(U$11-V+-Pad13)") (class "Default")
      (node (ref "U$11") (pin "13") (pinfunction "V+_13") (pintype "bidirectional"))
    )
    (net (code "113") (name "unconnected-(U$11-V--Pad4)") (class "Default")
      (node (ref "U$11") (pin "4") (pinfunction "V-_4") (pintype "bidirectional"))
    )
  )
)
